# MR_UartConnector.net
KiCad netlist of a schematic drawn in Altium Designer
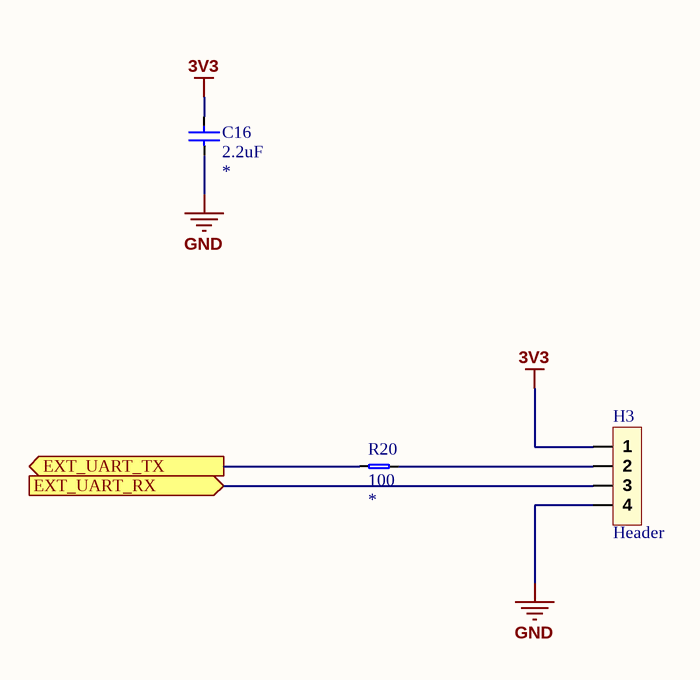
[diagram p0: MR_UartConnector.SchDoc]

(export (version "E")
  (design (tool "Eeschema 10.0.6"))
  (components
    (comp (ref "C16")
      (value "2.2uF")
      (footprint "0603_CAP_LD")
      (description "Ceramic Capacitor")
      (fields (field (name "PACKAGE") "*") (field (name "Comment") "CerCap"))
      (libsource (lib "MiniRobot") (part "CerCap"))
    )
    (comp (ref "H3")
      (value "Header")
      (footprint "HE14 1x4 Straight")
      (description "Header 4x1 PIns")
      (libsource (lib "MiniRobot") (part "Header_4x1"))
    )
    (comp (ref "R20")
      (value "100")
      (footprint "0603_RES_LD")
      (description "Resistor")
      (fields (field (name "PACKAGE") "*"))
      (libsource (lib "MiniRobot") (part "Resistor"))
    )
  )
  (nets
    (net (code "1") (name "/EXT_UART_RX") (class "Default")
      (node (ref "H3") (pin "3") (pinfunction "3_3") (pintype "passive"))
    )
    (net (code "2") (name "/EXT_UART_TX") (class "Default")
      (node (ref "R20") (pin "1") (pinfunction "1_1") (pintype "passive"))
    )
    (net (code "3") (name "3V3") (class "Default")
      (node (ref "C16") (pin "2") (pinfunction "2_2") (pintype "passive"))
      (node (ref "H3") (pin "1") (pinfunction "1_1") (pintype "passive"))
    )
    (net (code "4") (name "GND") (class "Default")
      (node (ref "C16") (pin "1") (pinfunction "1_1") (pintype "passive"))
      (node (ref "H3") (pin "4") (pinfunction "4_4") (pintype "passive"))
    )
    (net (code "5") (name "Net-(H3-Pad2)") (class "Default")
      (node (ref "H3") (pin "2") (pinfunction "2_2") (pintype "passive"))
      (node (ref "R20") (pin "2") (pinfunction "2_2") (pintype "passive"))
    )
  )
)
